# LM2596SCH.net
KiCad netlist of a schematic drawn in Altium Designer
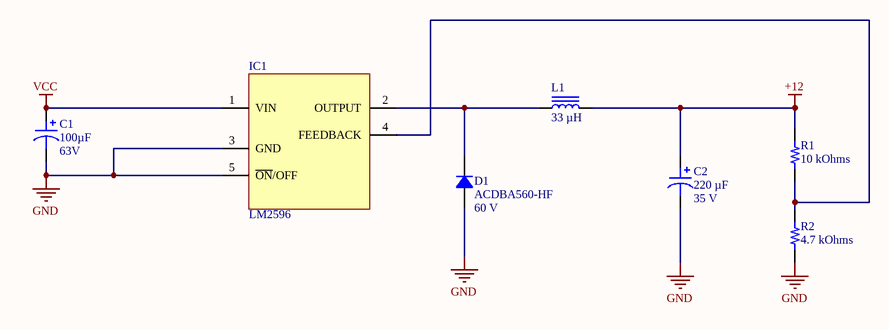
[diagram p0: LM2596SCH.SchDoc]

(export (version "E")
  (design (tool "Eeschema 10.0.6"))
  (components
    (comp (ref "C1")
      (value "100µF")
      (footprint "CAP TH ALUM ELEC D8.00mm S3.50mm H12.50mm")
      (description "CAP ALUM 100UF 20% 63V RADIAL")
      (fields
        (field (name "PART NUMBER") "ECA-1JM101")
        (field (name "MANUFACTURER") "Panasonic Electronic Components")
        (field (name "VOLTAGE - RATED") "63V")
      )
      (libsource (lib "Celestial Altium Library - altium_library") (part "Polarised Capacitor"))
    )
    (comp (ref "C2")
      (value "220 µF")
      (footprint "CAP AL TH D8 L3.5 H12.5")
      (description "CAP ALUM 220UF 20% 35V RADIAL")
      (fields
        (field (name "PART NUMBER") "ECA-1VM221")
        (field (name "MANUFACTURER") "Panasonic Electronic Components")
        (field (name "VOLTAGE - RATED") "35 V")
      )
      (libsource (lib "Celestial Altium Library - altium_library") (part "Polarised Capacitor"))
    )
    (comp (ref "D1")
      (value "ACDBA560-HF")
      (footprint "DO214AC SMA")
      (description "DIODE SCHOTTKY 60V 5A DO214AC")
      (fields
        (field (name "MANUFACTURER") "Comchip Technology")
        (field (name "VOLTAGE - DC REVERSE (VR) (MAX)") "60 V")
      )
      (libsource (lib "Celestial Altium Library - altium_library") (part "Diode"))
    )
    (comp (ref "IC1") (value "LM2596") (footprint "LM2596:LM2596") (libsource (lib "LM2596") (part "LM2596")))
    (comp (ref "L1")
      (value "33 µH")
      (footprint "BOURNS SRR1280")
      (description "FIXED IND 33UH 3.5A 57 MOHM SMD")
      (fields (field (name "PART NUMBER") "SRR1280-330M") (field (name "MANUFACTURER") "Bourns Inc."))
      (libsource (lib "Celestial Altium Library - altium_library") (part "Inductor"))
    )
    (comp (ref "R1")
      (value "10 kOhms")
      (footprint "RES 0805_2012")
      (description "RES 10K OHM 0.1% 1/10W 0805")
      (fields
        (field (name "PART NUMBER") "RNCS0805BKE10K0")
        (field (name "MANUFACTURER") "Stackpole Electronics Inc")
      )
      (libsource (lib "Celestial Altium Library - altium_library") (part "Resistor"))
    )
    (comp (ref "R2")
      (value "4.7 kOhms")
      (footprint "RES 0805_2012")
      (description "RES 4.7K OHM 1% 1/3W 0805")
      (fields
        (field (name "PART NUMBER") "CRGP0805F4K7")
        (field (name "MANUFACTURER") "TE Connectivity Passive Product")
      )
      (libsource (lib "Celestial Altium Library - altium_library") (part "Resistor"))
    )
  )
  (nets
    (net (code "1") (name "+12") (class "Default")
      (node (ref "C2") (pin "1") (pinfunction "1_1") (pintype "passive"))
      (node (ref "L1") (pin "2") (pinfunction "2_2") (pintype "passive"))
      (node (ref "R1") (pin "2") (pinfunction "2_2") (pintype "passive"))
    )
    (net (code "2") (name "GND") (class "Default")
      (node (ref "C1") (pin "2") (pinfunction "2_2") (pintype "passive"))
      (node (ref "C2") (pin "2") (pinfunction "2_2") (pintype "passive"))
      (node (ref "D1") (pin "1") (pinfunction "1_1") (pintype "passive"))
      (node (ref "IC1") (pin "3") (pinfunction "GND_3") (pintype "passive"))
      (node (ref "IC1") (pin "5") (pinfunction "~{ON}/OFF_5") (pintype "passive"))
      (node (ref "R2") (pin "1") (pinfunction "1_1") (pintype "passive"))
    )
    (net (code "3") (name "Net-(IC1-FEEDBACK)") (class "Default")
      (node (ref "IC1") (pin "4") (pinfunction "FEEDBACK_4") (pintype "passive"))
      (node (ref "R1") (pin "1") (pinfunction "1_1") (pintype "passive"))
      (node (ref "R2") (pin "2") (pinfunction "2_2") (pintype "passive"))
    )
    (net (code "4") (name "Net-(IC1-OUTPUT)") (class "Default")
      (node (ref "D1") (pin "2") (pinfunction "2_2") (pintype "passive"))
      (node (ref "IC1") (pin "2") (pinfunction "OUTPUT_2") (pintype "passive"))
      (node (ref "L1") (pin "1") (pinfunction "1_1") (pintype "passive"))
    )
    (net (code "5") (name "VCC") (class "Default")
      (node (ref "C1") (pin "1") (pinfunction "1_1") (pintype "passive"))
      (node (ref "IC1") (pin "1") (pinfunction "VIN_1") (pintype "passive"))
    )
  )
)
